# TPS54360.net
KiCad netlist of a schematic drawn in Altium Designer
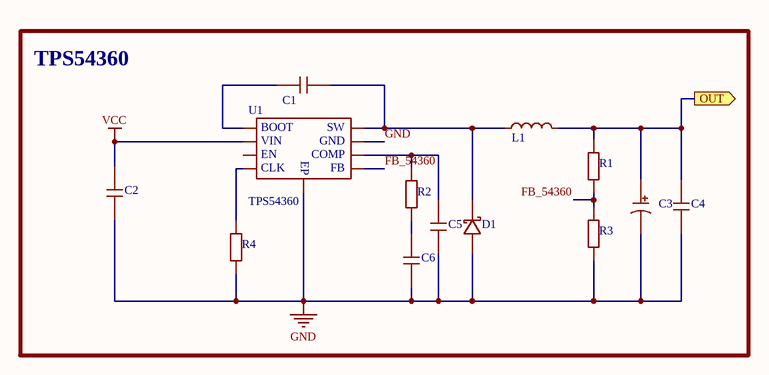
[diagram p0: TPS54360.SchDoc]

(export (version "E")
  (design (tool "Eeschema 10.0.6"))
  (components
    (comp (ref "C1") (value "100nF") (footprint "0603C") (libsource (lib "元件库") (part "电容_贴片")))
    (comp (ref "C2") (value "4.7uF") (footprint "0805C") (libsource (lib "元件库") (part "电容_贴片")))
    (comp (ref "C3") (value "钽电容") (footprint "3528B/1210") (libsource (lib "元件库") (part "电容_贴片钽")))
    (comp (ref "C4") (value "47uF") (footprint "0805C") (libsource (lib "元件库") (part "电容_贴片")))
    (comp (ref "C5") (value "4.7nF") (footprint "0603C") (libsource (lib "元件库") (part "电容_贴片")))
    (comp (ref "C6") (value "4.7nF") (footprint "0603C") (libsource (lib "元件库") (part "电容_贴片")))
    (comp (ref "D1") (value "SS56") (footprint "SMA") (libsource (lib "元件库") (part "二极管_肖特基")))
    (comp (ref "L1") (value "10uH") (footprint "0630L") (libsource (lib "元件库") (part "电感_贴片")))
    (comp (ref "R1") (value "60.4K") (footprint "0603R") (libsource (lib "") (part "电阻_贴片_1")))
    (comp (ref "R2") (value "28.7K") (footprint "0603R") (libsource (lib "") (part "电阻_贴片_1")))
    (comp (ref "R3") (value "11.5K") (footprint "0603R") (libsource (lib "") (part "电阻_贴片_1")))
    (comp (ref "R4") (value "124K") (footprint "0603R") (libsource (lib "元件库") (part "电阻_贴片")))
    (comp (ref "U1")
      (value "TPS54360")
      (footprint "SOP-8-PP")
      (libsource (lib "元件库") (part "芯片/IC-电源管理-TPS54360"))
    )
  )
  (nets
    (net (code "1") (name "/FB_54360") (class "Default")
      (node (ref "R1") (pin "1") (pinfunction "1_1") (pintype "passive"))
      (node (ref "R3") (pin "2") (pinfunction "2_2") (pintype "passive"))
      (node (ref "U1") (pin "5") (pinfunction "5_5") (pintype "passive"))
    )
    (net (code "2") (name "/OUT") (class "Default")
      (node (ref "C3") (pin "1") (pinfunction "1_1") (pintype "passive"))
      (node (ref "C4") (pin "2") (pinfunction "2_2") (pintype "passive"))
      (node (ref "L1") (pin "2") (pinfunction "2_2") (pintype "passive"))
      (node (ref "R1") (pin "2") (pinfunction "2_2") (pintype "passive"))
    )
    (net (code "3") (name "GND") (class "Default")
      (node (ref "C2") (pin "1") (pinfunction "1_1") (pintype "passive"))
      (node (ref "C3") (pin "2") (pinfunction "2_2") (pintype "passive"))
      (node (ref "C4") (pin "1") (pinfunction "1_1") (pintype "passive"))
      (node (ref "C5") (pin "2") (pinfunction "2_2") (pintype "passive"))
      (node (ref "C6") (pin "2") (pinfunction "2_2") (pintype "passive"))
      (node (ref "D1") (pin "1") (pinfunction "1_1") (pintype "passive"))
      (node (ref "R3") (pin "1") (pinfunction "1_1") (pintype "passive"))
      (node (ref "R4") (pin "1") (pinfunction "1_1") (pintype "passive"))
      (node (ref "U1") (pin "7") (pinfunction "7_7") (pintype "passive"))
      (node (ref "U1") (pin "9") (pinfunction "9_9") (pintype "passive"))
    )
    (net (code "4") (name "Net-(C1-Pad1)") (class "Default")
      (node (ref "C1") (pin "1") (pinfunction "1_1") (pintype "passive"))
      (node (ref "D1") (pin "2") (pinfunction "2_2") (pintype "passive"))
      (node (ref "L1") (pin "1") (pinfunction "1_1") (pintype "passive"))
      (node (ref "U1") (pin "8") (pinfunction "8_8") (pintype "passive"))
    )
    (net (code "5") (name "Net-(C1-Pad2)") (class "Default")
      (node (ref "C1") (pin "2") (pinfunction "2_2") (pintype "passive"))
      (node (ref "U1") (pin "1") (pinfunction "1_1") (pintype "passive"))
    )
    (net (code "6") (name "Net-(C5-Pad1)") (class "Default")
      (node (ref "C5") (pin "1") (pinfunction "1_1") (pintype "passive"))
      (node (ref "R2") (pin "2") (pinfunction "2_2") (pintype "passive"))
      (node (ref "U1") (pin "6") (pinfunction "6_6") (pintype "passive"))
    )
    (net (code "7") (name "Net-(C6-Pad1)") (class "Default")
      (node (ref "C6") (pin "1") (pinfunction "1_1") (pintype "passive"))
      (node (ref "R2") (pin "1") (pinfunction "1_1") (pintype "passive"))
    )
    (net (code "8") (name "Net-(R4-Pad2)") (class "Default")
      (node (ref "R4") (pin "2") (pinfunction "2_2") (pintype "passive"))
      (node (ref "U1") (pin "4") (pinfunction "4_4") (pintype "passive"))
    )
    (net (code "9") (name "VCC") (class "Default")
      (node (ref "C2") (pin "2") (pinfunction "2_2") (pintype "passive"))
      (node (ref "U1") (pin "2") (pinfunction "2_2") (pintype "passive"))
    )
    (net (code "10") (name "unconnected-(U1-Pad3)") (class "Default")
      (node (ref "U1") (pin "3") (pinfunction "3_3") (pintype "passive"))
    )
  )
)
